# MCU.net
KiCad netlist of a schematic drawn in Altium Designer
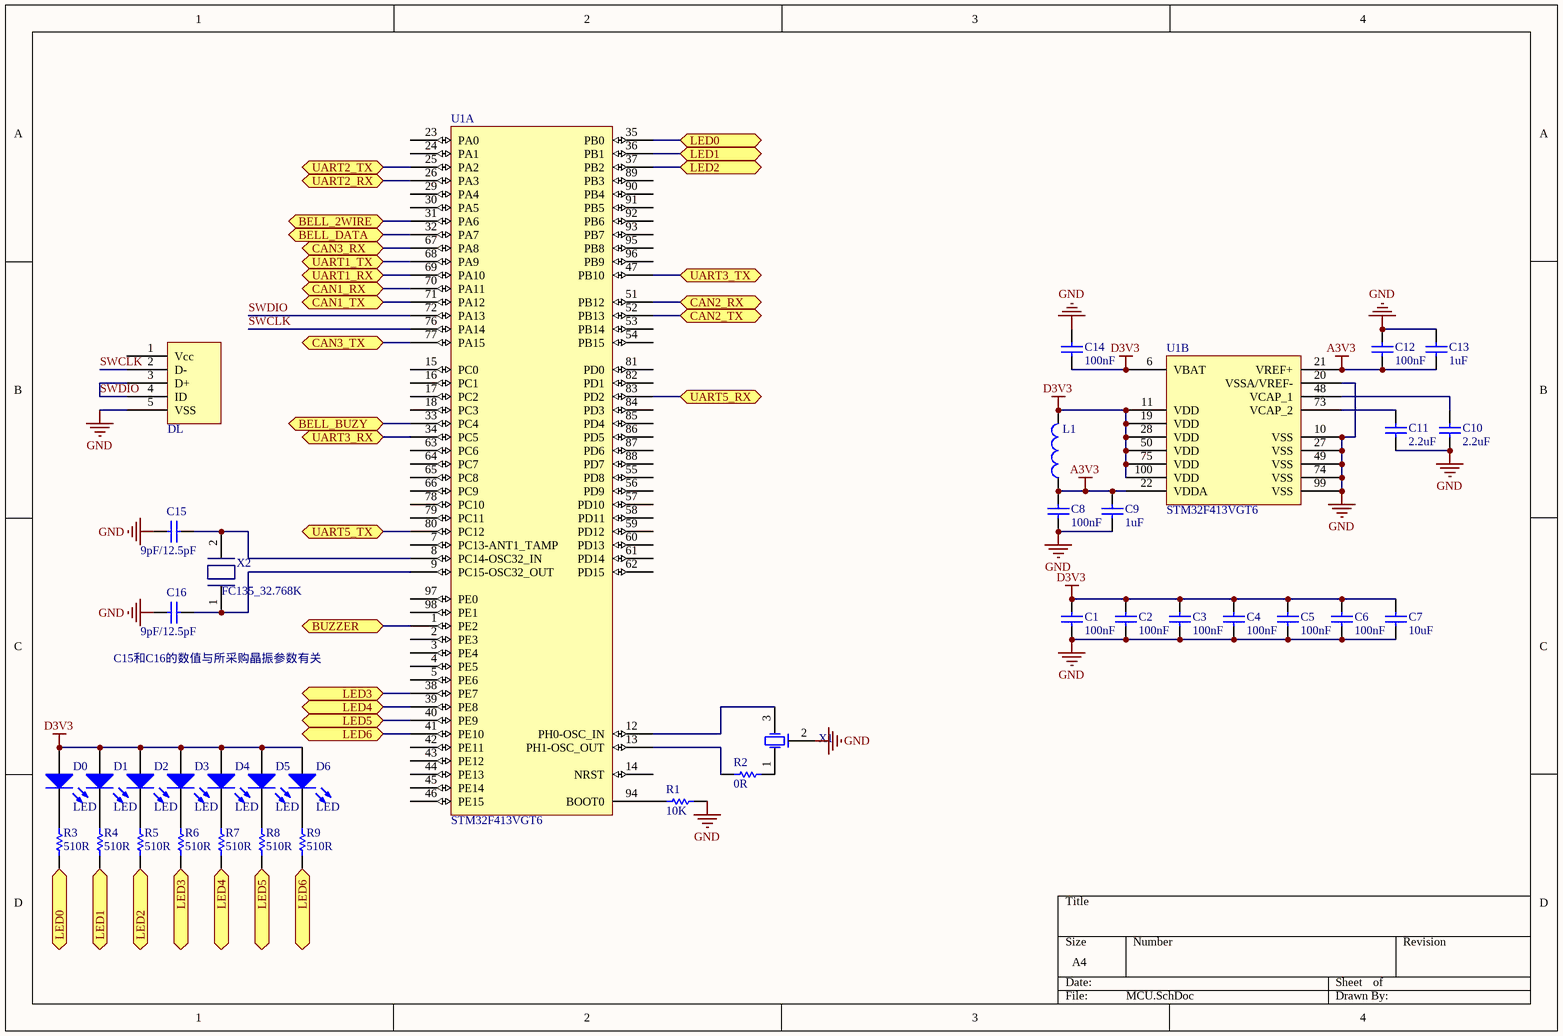
[diagram p0: MCU.SchDoc]

(export (version "E")
  (design (tool "Eeschema 10.0.6"))
  (components
    (comp (ref "C1")
      (value "100nF")
      (footprint "BinFeng:0402")
      (description "Capacitor")
      (fields (field (name "PUBLISHER") "Altium Limited"))
      (libsource (lib "Miscellaneous Devices") (part "Cap"))
    )
    (comp (ref "C2")
      (value "100nF")
      (footprint "BinFeng:0402")
      (description "Capacitor")
      (fields (field (name "PUBLISHER") "Altium Limited"))
      (libsource (lib "Miscellaneous Devices") (part "Cap"))
    )
    (comp (ref "C3")
      (value "100nF")
      (footprint "BinFeng:0402")
      (description "Capacitor")
      (fields (field (name "PUBLISHER") "Altium Limited"))
      (libsource (lib "Miscellaneous Devices") (part "Cap"))
    )
    (comp (ref "C4")
      (value "100nF")
      (footprint "BinFeng:0402")
      (description "Capacitor")
      (fields (field (name "PUBLISHER") "Altium Limited"))
      (libsource (lib "Miscellaneous Devices") (part "Cap"))
    )
    (comp (ref "C5")
      (value "100nF")
      (footprint "BinFeng:0402")
      (description "Capacitor")
      (fields (field (name "PUBLISHER") "Altium Limited"))
      (libsource (lib "Miscellaneous Devices") (part "Cap"))
    )
    (comp (ref "C6")
      (value "100nF")
      (footprint "BinFeng:0402")
      (description "Capacitor")
      (fields (field (name "PUBLISHER") "Altium Limited"))
      (libsource (lib "Miscellaneous Devices") (part "Cap"))
    )
    (comp (ref "C7")
      (value "10uF")
      (footprint "0805")
      (description "Capacitor")
      (fields (field (name "PUBLISHER") "Altium Limited"))
      (libsource (lib "Miscellaneous Devices") (part "Cap"))
    )
    (comp (ref "C8")
      (value "100nF")
      (footprint "BinFeng:0402")
      (description "Capacitor")
      (fields (field (name "PUBLISHER") "Altium Limited"))
      (libsource (lib "Miscellaneous Devices") (part "Cap"))
    )
    (comp (ref "C9")
      (value "1uF")
      (footprint "BinFeng:0402")
      (description "Capacitor")
      (fields (field (name "PUBLISHER") "Altium Limited"))
      (libsource (lib "Miscellaneous Devices") (part "Cap"))
    )
    (comp (ref "C10")
      (value "2.2uF")
      (footprint "BinFeng:0603")
      (description "Capacitor")
      (fields (field (name "PUBLISHER") "Altium Limited"))
      (libsource (lib "Miscellaneous Devices") (part "Cap"))
    )
    (comp (ref "C11")
      (value "2.2uF")
      (footprint "BinFeng:0603")
      (description "Capacitor")
      (fields (field (name "PUBLISHER") "Altium Limited"))
      (libsource (lib "Miscellaneous Devices") (part "Cap"))
    )
    (comp (ref "C12")
      (value "100nF")
      (footprint "BinFeng:0402")
      (description "Capacitor")
      (fields (field (name "PUBLISHER") "Altium Limited"))
      (libsource (lib "Miscellaneous Devices") (part "Cap"))
    )
    (comp (ref "C13")
      (value "1uF")
      (footprint "BinFeng:0402")
      (description "Capacitor")
      (fields (field (name "PUBLISHER") "Altium Limited"))
      (libsource (lib "Miscellaneous Devices") (part "Cap"))
    )
    (comp (ref "C14")
      (value "100nF")
      (footprint "BinFeng:0402")
      (description "Capacitor")
      (fields (field (name "PUBLISHER") "Altium Limited"))
      (libsource (lib "Miscellaneous Devices") (part "Cap"))
    )
    (comp (ref "C15")
      (value "9pF/12.5pF")
      (footprint "BinFeng:0402")
      (description "Capacitor")
      (fields (field (name "PUBLISHER") "Altium Limited"))
      (libsource (lib "Miscellaneous Devices") (part "Cap"))
    )
    (comp (ref "C16")
      (value "9pF/12.5pF")
      (footprint "BinFeng:0402")
      (description "Capacitor")
      (fields (field (name "PUBLISHER") "Altium Limited"))
      (libsource (lib "Miscellaneous Devices") (part "Cap"))
    )
    (comp (ref "D0")
      (value "LED")
      (footprint "1206")
      (description "green LED")
      (fields (field (name "PUBLISHER") "Altium Limited"))
      (libsource (lib "Miscellaneous Devices") (part "LED0"))
    )
    (comp (ref "D1")
      (value "LED")
      (footprint "1206")
      (description "green LED")
      (fields (field (name "PUBLISHER") "Altium Limited"))
      (libsource (lib "Miscellaneous Devices") (part "LED0"))
    )
    (comp (ref "D2")
      (value "LED")
      (footprint "1206")
      (description "green LED")
      (fields (field (name "PUBLISHER") "Altium Limited"))
      (libsource (lib "Miscellaneous Devices") (part "LED0"))
    )
    (comp (ref "D3")
      (value "LED")
      (footprint "1206")
      (description "green LED")
      (fields (field (name "PUBLISHER") "Altium Limited"))
      (libsource (lib "Miscellaneous Devices") (part "LED0"))
    )
    (comp (ref "D4")
      (value "LED")
      (footprint "1206")
      (description "green LED")
      (fields (field (name "PUBLISHER") "Altium Limited"))
      (libsource (lib "Miscellaneous Devices") (part "LED0"))
    )
    (comp (ref "D5")
      (value "LED")
      (footprint "1206")
      (description "green LED")
      (fields (field (name "PUBLISHER") "Altium Limited"))
      (libsource (lib "Miscellaneous Devices") (part "LED0"))
    )
    (comp (ref "D6")
      (value "LED")
      (footprint "1206")
      (description "green LED")
      (fields (field (name "PUBLISHER") "Altium Limited"))
      (libsource (lib "Miscellaneous Devices") (part "LED0"))
    )
    (comp (ref "DL")
      (value "USB_5pin")
      (footprint "USBmicro_B")
      (libsource (lib "BinFeng_Connectors") (part "USB_5pin"))
    )
    (comp (ref "L1")
      (value "BLM15BD221SN1D")
      (footprint "BinFeng:0402")
      (description "muRata ferrite bead")
      (fields (field (name "PUBLISHER") "Altium Limited"))
      (libsource (lib "Miscellaneous Devices") (part "Inductor"))
    )
    (comp (ref "R1")
      (value "10K")
      (footprint "BinFeng:0402")
      (description "Resistor")
      (fields (field (name "PUBLISHER") "Altium Limited"))
      (libsource (lib "Miscellaneous Devices") (part "Res1"))
    )
    (comp (ref "R2")
      (value "0R")
      (footprint "BinFeng:0402")
      (description "Resistor")
      (fields (field (name "PUBLISHER") "Altium Limited"))
      (libsource (lib "Miscellaneous Devices") (part "Res1"))
    )
    (comp (ref "R3")
      (value "510R")
      (footprint "BinFeng:0402")
      (description "Resistor")
      (fields (field (name "PUBLISHER") "Altium Limited"))
      (libsource (lib "Miscellaneous Devices") (part "Res1"))
    )
    (comp (ref "R4")
      (value "510R")
      (footprint "BinFeng:0402")
      (description "Resistor")
      (fields (field (name "PUBLISHER") "Altium Limited"))
      (libsource (lib "Miscellaneous Devices") (part "Res1"))
    )
    (comp (ref "R5")
      (value "510R")
      (footprint "BinFeng:0402")
      (description "Resistor")
      (fields (field (name "PUBLISHER") "Altium Limited"))
      (libsource (lib "Miscellaneous Devices") (part "Res1"))
    )
    (comp (ref "R6")
      (value "510R")
      (footprint "BinFeng:0402")
      (description "Resistor")
      (fields (field (name "PUBLISHER") "Altium Limited"))
      (libsource (lib "Miscellaneous Devices") (part "Res1"))
    )
    (comp (ref "R7")
      (value "510R")
      (footprint "BinFeng:0402")
      (description "Resistor")
      (fields (field (name "PUBLISHER") "Altium Limited"))
      (libsource (lib "Miscellaneous Devices") (part "Res1"))
    )
    (comp (ref "R8")
      (value "510R")
      (footprint "BinFeng:0402")
      (description "Resistor")
      (fields (field (name "PUBLISHER") "Altium Limited"))
      (libsource (lib "Miscellaneous Devices") (part "Res1"))
    )
    (comp (ref "R9")
      (value "510R")
      (footprint "BinFeng:0402")
      (description "Resistor")
      (fields (field (name "PUBLISHER") "Altium Limited"))
      (libsource (lib "Miscellaneous Devices") (part "Res1"))
    )
    (comp (ref "U1")
      (value "STM32F413VGT6")
      (footprint "STM-LQFP100_V")
      (description "ARM Cortex-M4 32-Bit DSP+FPU, 1024 KB Flash, 82 I/Os, 100-Pin LQFP, -40 to 85 degC, Tray")
      (libsource (lib "Altium Content Vault") (part "STM-STM32F413-LQFP-100"))
    )
    (comp (ref "X1")
      (value "8M smd")
      (footprint "8Mhz_XTAL")
      (description "muRata")
      (libsource (lib "Schlib1") (part "8M smd"))
    )
    (comp (ref "X2")
      (value "FC135_32.768K")
      (footprint "FC135")
      (libsource (lib "BinFeng_IC") (part "XTAL_32.768k"))
    )
  )
  (nets
    (net (code "1") (name "/BELL_2WIRE") (class "Default")
      (node (ref "U1") (pin "31") (pinfunction "PA6_31") (pintype "bidirectional"))
    )
    (net (code "2") (name "/BELL_BUZY") (class "Default")
      (node (ref "U1") (pin "33") (pinfunction "PC4_33") (pintype "bidirectional"))
    )
    (net (code "3") (name "/BELL_DATA") (class "Default")
      (node (ref "U1") (pin "32") (pinfunction "PA7_32") (pintype "bidirectional"))
    )
    (net (code "4") (name "/BUZZER") (class "Default")
      (node (ref "U1") (pin "1") (pinfunction "PE2_1") (pintype "bidirectional"))
    )
    (net (code "5") (name "/CAN1_RX") (class "Default")
      (node (ref "U1") (pin "70") (pinfunction "PA11_70") (pintype "bidirectional"))
    )
    (net (code "6") (name "/CAN1_TX") (class "Default")
      (node (ref "U1") (pin "71") (pinfunction "PA12_71") (pintype "bidirectional"))
    )
    (net (code "7") (name "/CAN2_RX") (class "Default")
      (node (ref "U1") (pin "51") (pinfunction "PB12_51") (pintype "bidirectional"))
    )
    (net (code "8") (name "/CAN2_TX") (class "Default")
      (node (ref "U1") (pin "52") (pinfunction "PB13_52") (pintype "bidirectional"))
    )
    (net (code "9") (name "/CAN3_RX") (class "Default")
      (node (ref "U1") (pin "67") (pinfunction "PA8_67") (pintype "bidirectional"))
    )
    (net (code "10") (name "/CAN3_TX") (class "Default")
      (node (ref "U1") (pin "77") (pinfunction "PA15_77") (pintype "bidirectional"))
    )
    (net (code "11") (name "/LED0") (class "Default")
      (node (ref "R3") (pin "1") (pinfunction "1_1") (pintype "passive"))
      (node (ref "U1") (pin "35") (pinfunction "PB0_35") (pintype "bidirectional"))
    )
    (net (code "12") (name "/LED1") (class "Default")
      (node (ref "R4") (pin "1") (pinfunction "1_1") (pintype "passive"))
      (node (ref "U1") (pin "36") (pinfunction "PB1_36") (pintype "bidirectional"))
    )
    (net (code "13") (name "/LED2") (class "Default")
      (node (ref "R5") (pin "1") (pinfunction "1_1") (pintype "passive"))
      (node (ref "U1") (pin "37") (pinfunction "PB2_37") (pintype "bidirectional"))
    )
    (net (code "14") (name "/LED3") (class "Default")
      (node (ref "R6") (pin "1") (pinfunction "1_1") (pintype "passive"))
      (node (ref "U1") (pin "38") (pinfunction "PE7_38") (pintype "bidirectional"))
    )
    (net (code "15") (name "/LED4") (class "Default")
      (node (ref "R7") (pin "1") (pinfunction "1_1") (pintype "passive"))
      (node (ref "U1") (pin "39") (pinfunction "PE8_39") (pintype "bidirectional"))
    )
    (net (code "16") (name "/LED5") (class "Default")
      (node (ref "R8") (pin "1") (pinfunction "1_1") (pintype "passive"))
      (node (ref "U1") (pin "40") (pinfunction "PE9_40") (pintype "bidirectional"))
    )
    (net (code "17") (name "/LED6") (class "Default")
      (node (ref "R9") (pin "1") (pinfunction "1_1") (pintype "passive"))
      (node (ref "U1") (pin "41") (pinfunction "PE10_41") (pintype "bidirectional"))
    )
    (net (code "18") (name "/SWCLK") (class "Default")
      (node (ref "DL") (pin "2") (pinfunction "D-_2") (pintype "passive"))
      (node (ref "U1") (pin "76") (pinfunction "PA14_76") (pintype "bidirectional"))
    )
    (net (code "19") (name "/SWDIO") (class "Default")
      (node (ref "DL") (pin "3") (pinfunction "D+_3") (pintype "passive"))
      (node (ref "DL") (pin "4") (pinfunction "ID_4") (pintype "passive"))
      (node (ref "U1") (pin "72") (pinfunction "PA13_72") (pintype "bidirectional"))
    )
    (net (code "20") (name "/UART1_RX") (class "Default")
      (node (ref "U1") (pin "69") (pinfunction "PA10_69") (pintype "bidirectional"))
    )
    (net (code "21") (name "/UART1_TX") (class "Default")
      (node (ref "U1") (pin "68") (pinfunction "PA9_68") (pintype "bidirectional"))
    )
    (net (code "22") (name "/UART2_RX") (class "Default")
      (node (ref "U1") (pin "26") (pinfunction "PA3_26") (pintype "bidirectional"))
    )
    (net (code "23") (name "/UART2_TX") (class "Default")
      (node (ref "U1") (pin "25") (pinfunction "PA2_25") (pintype "bidirectional"))
    )
    (net (code "24") (name "/UART3_RX") (class "Default")
      (node (ref "U1") (pin "34") (pinfunction "PC5_34") (pintype "bidirectional"))
    )
    (net (code "25") (name "/UART3_TX") (class "Default")
      (node (ref "U1") (pin "47") (pinfunction "PB10_47") (pintype "bidirectional"))
    )
    (net (code "26") (name "/UART5_RX") (class "Default")
      (node (ref "U1") (pin "83") (pinfunction "PD2_83") (pintype "bidirectional"))
    )
    (net (code "27") (name "/UART5_TX") (class "Default")
      (node (ref "U1") (pin "80") (pinfunction "PC12_80") (pintype "bidirectional"))
    )
    (net (code "28") (name "A3V3") (class "Default")
      (node (ref "C12") (pin "1") (pinfunction "1_1") (pintype "passive"))
      (node (ref "C13") (pin "1") (pinfunction "1_1") (pintype "passive"))
      (node (ref "C8") (pin "2") (pinfunction "2_2") (pintype "passive"))
      (node (ref "C9") (pin "2") (pinfunction "2_2") (pintype "passive"))
      (node (ref "L1") (pin "1") (pinfunction "1_1") (pintype "passive"))
      (node (ref "U1") (pin "21") (pinfunction "VREF+_21") (pintype "power_in"))
      (node (ref "U1") (pin "22") (pinfunction "VDDA_22") (pintype "power_in"))
    )
    (net (code "29") (name "D3V3") (class "Default")
      (node (ref "C1") (pin "2") (pinfunction "2_2") (pintype "passive"))
      (node (ref "C14") (pin "1") (pinfunction "1_1") (pintype "passive"))
      (node (ref "C2") (pin "2") (pinfunction "2_2") (pintype "passive"))
      (node (ref "C3") (pin "2") (pinfunction "2_2") (pintype "passive"))
      (node (ref "C4") (pin "2") (pinfunction "2_2") (pintype "passive"))
      (node (ref "C5") (pin "2") (pinfunction "2_2") (pintype "passive"))
      (node (ref "C6") (pin "2") (pinfunction "2_2") (pintype "passive"))
      (node (ref "C7") (pin "2") (pinfunction "2_2") (pintype "passive"))
      (node (ref "D0") (pin "1") (pinfunction "A_1") (pintype "passive"))
      (node (ref "D1") (pin "1") (pinfunction "A_1") (pintype "passive"))
      (node (ref "D2") (pin "1") (pinfunction "A_1") (pintype "passive"))
      (node (ref "D3") (pin "1") (pinfunction "A_1") (pintype "passive"))
      (node (ref "D4") (pin "1") (pinfunction "A_1") (pintype "passive"))
      (node (ref "D5") (pin "1") (pinfunction "A_1") (pintype "passive"))
      (node (ref "D6") (pin "1") (pinfunction "A_1") (pintype "passive"))
      (node (ref "L1") (pin "2") (pinfunction "2_2") (pintype "passive"))
      (node (ref "U1") (pin "100") (pinfunction "VDD_100") (pintype "power_in"))
      (node (ref "U1") (pin "11") (pinfunction "VDD_11") (pintype "power_in"))
      (node (ref "U1") (pin "19") (pinfunction "VDD_19") (pintype "power_in"))
      (node (ref "U1") (pin "28") (pinfunction "VDD_28") (pintype "power_in"))
      (node (ref "U1") (pin "50") (pinfunction "VDD_50") (pintype "power_in"))
      (node (ref "U1") (pin "6") (pinfunction "VBAT_6") (pintype "power_in"))
      (node (ref "U1") (pin "75") (pinfunction "VDD_75") (pintype "power_in"))
    )
    (net (code "30") (name "GND") (class "Default")
      (node (ref "C1") (pin "1") (pinfunction "1_1") (pintype "passive"))
      (node (ref "C10") (pin "1") (pinfunction "1_1") (pintype "passive"))
      (node (ref "C11") (pin "1") (pinfunction "1_1") (pintype "passive"))
      (node (ref "C12") (pin "2") (pinfunction "2_2") (pintype "passive"))
      (node (ref "C13") (pin "2") (pinfunction "2_2") (pintype "passive"))
      (node (ref "C14") (pin "2") (pinfunction "2_2") (pintype "passive"))
      (node (ref "C15") (pin "2") (pinfunction "2_2") (pintype "passive"))
      (node (ref "C16") (pin "2") (pinfunction "2_2") (pintype "passive"))
      (node (ref "C2") (pin "1") (pinfunction "1_1") (pintype "passive"))
      (node (ref "C3") (pin "1") (pinfunction "1_1") (pintype "passive"))
      (node (ref "C4") (pin "1") (pinfunction "1_1") (pintype "passive"))
      (node (ref "C5") (pin "1") (pinfunction "1_1") (pintype "passive"))
      (node (ref "C6") (pin "1") (pinfunction "1_1") (pintype "passive"))
      (node (ref "C7") (pin "1") (pinfunction "1_1") (pintype "passive"))
      (node (ref "C8") (pin "1") (pinfunction "1_1") (pintype "passive"))
      (node (ref "C9") (pin "1") (pinfunction "1_1") (pintype "passive"))
      (node (ref "DL") (pin "5") (pinfunction "VSS_5") (pintype "passive"))
      (node (ref "R1") (pin "2") (pinfunction "2_2") (pintype "passive"))
      (node (ref "U1") (pin "10") (pinfunction "VSS_10") (pintype "power_in"))
      (node (ref "U1") (pin "20") (pinfunction "VSSA/VREF-_20") (pintype "power_in"))
      (node (ref "U1") (pin "27") (pinfunction "VSS_27") (pintype "power_in"))
      (node (ref "U1") (pin "49") (pinfunction "VSS_49") (pintype "power_in"))
      (node (ref "U1") (pin "74") (pinfunction "VSS_74") (pintype "power_in"))
      (node (ref "U1") (pin "99") (pinfunction "VSS_99") (pintype "power_in"))
      (node (ref "X1") (pin "2") (pinfunction "GND_2") (pintype "passive"))
    )
    (net (code "31") (name "Net-(D0-K)") (class "Default")
      (node (ref "D0") (pin "2") (pinfunction "K_2") (pintype "passive"))
      (node (ref "R3") (pin "2") (pinfunction "2_2") (pintype "passive"))
    )
    (net (code "32") (name "Net-(D1-K)") (class "Default")
      (node (ref "D1") (pin "2") (pinfunction "K_2") (pintype "passive"))
      (node (ref "R4") (pin "2") (pinfunction "2_2") (pintype "passive"))
    )
    (net (code "33") (name "Net-(D2-K)") (class "Default")
      (node (ref "D2") (pin "2") (pinfunction "K_2") (pintype "passive"))
      (node (ref "R5") (pin "2") (pinfunction "2_2") (pintype "passive"))
    )
    (net (code "34") (name "Net-(D3-K)") (class "Default")
      (node (ref "D3") (pin "2") (pinfunction "K_2") (pintype "passive"))
      (node (ref "R6") (pin "2") (pinfunction "2_2") (pintype "passive"))
    )
    (net (code "35") (name "Net-(D4-K)") (class "Default")
      (node (ref "D4") (pin "2") (pinfunction "K_2") (pintype "passive"))
      (node (ref "R7") (pin "2") (pinfunction "2_2") (pintype "passive"))
    )
    (net (code "36") (name "Net-(D5-K)") (class "Default")
      (node (ref "D5") (pin "2") (pinfunction "K_2") (pintype "passive"))
      (node (ref "R8") (pin "2") (pinfunction "2_2") (pintype "passive"))
    )
    (net (code "37") (name "Net-(D6-K)") (class "Default")
      (node (ref "D6") (pin "2") (pinfunction "K_2") (pintype "passive"))
      (node (ref "R9") (pin "2") (pinfunction "2_2") (pintype "passive"))
    )
    (net (code "38") (name "Net-(U1A-BOOT0)") (class "Default")
      (node (ref "R1") (pin "1") (pinfunction "1_1") (pintype "passive"))
      (node (ref "U1") (pin "94") (pinfunction "BOOT0_94") (pintype "passive"))
    )
    (net (code "39") (name "Net-(U1A-PC14-OSC32_IN)") (class "Default")
      (node (ref "C15") (pin "1") (pinfunction "1_1") (pintype "passive"))
      (node (ref "U1") (pin "8") (pinfunction "PC14-OSC32_IN_8") (pintype "bidirectional"))
      (node (ref "X2") (pin "2") (pinfunction "2_2") (pintype "passive"))
    )
    (net (code "40") (name "Net-(U1A-PC15-OSC32_OUT)") (class "Default")
      (node (ref "C16") (pin "1") (pinfunction "1_1") (pintype "passive"))
      (node (ref "U1") (pin "9") (pinfunction "PC15-OSC32_OUT_9") (pintype "bidirectional"))
      (node (ref "X2") (pin "1") (pinfunction "1_1") (pintype "passive"))
    )
    (net (code "41") (name "Net-(U1A-PH0-OSC_IN)") (class "Default")
      (node (ref "U1") (pin "12") (pinfunction "PH0-OSC_IN_12") (pintype "bidirectional"))
      (node (ref "X1") (pin "3") (pinfunction "OSC2_3") (pintype "passive"))
    )
    (net (code "42") (name "Net-(U1A-PH1-OSC_OUT)") (class "Default")
      (node (ref "R2") (pin "2") (pinfunction "2_2") (pintype "passive"))
      (node (ref "U1") (pin "13") (pinfunction "PH1-OSC_OUT_13") (pintype "bidirectional"))
    )
    (net (code "43") (name "Net-(U1B-VCAP_1)") (class "Default")
      (node (ref "C10") (pin "2") (pinfunction "2_2") (pintype "passive"))
      (node (ref "U1") (pin "48") (pinfunction "VCAP_1_48") (pintype "passive"))
    )
    (net (code "44") (name "Net-(U1B-VCAP_2)") (class "Default")
      (node (ref "C11") (pin "2") (pinfunction "2_2") (pintype "passive"))
      (node (ref "U1") (pin "73") (pinfunction "VCAP_2_73") (pintype "passive"))
    )
    (net (code "45") (name "Net-(X1-OSC1)") (class "Default")
      (node (ref "R2") (pin "1") (pinfunction "1_1") (pintype "passive"))
      (node (ref "X1") (pin "1") (pinfunction "OSC1_1") (pintype "passive"))
    )
    (net (code "46") (name "unconnected-(DL-Vcc-Pad1)") (class "Default")
      (node (ref "DL") (pin "1") (pinfunction "Vcc_1") (pintype "passive"))
    )
    (net (code "47") (name "unconnected-(U1A-NRST-Pad14)") (class "Default")
      (node (ref "U1") (pin "14") (pinfunction "NRST_14") (pintype "bidirectional"))
    )
    (net (code "48") (name "unconnected-(U1A-PA0-Pad23)") (class "Default")
      (node (ref "U1") (pin "23") (pinfunction "PA0_23") (pintype "bidirectional"))
    )
    (net (code "49") (name "unconnected-(U1A-PA1-Pad24)") (class "Default")
      (node (ref "U1") (pin "24") (pinfunction "PA1_24") (pintype "bidirectional"))
    )
    (net (code "50") (name "unconnected-(U1A-PA4-Pad29)") (class "Default")
      (node (ref "U1") (pin "29") (pinfunction "PA4_29") (pintype "bidirectional"))
    )
    (net (code "51") (name "unconnected-(U1A-PA5-Pad30)") (class "Default")
      (node (ref "U1") (pin "30") (pinfunction "PA5_30") (pintype "bidirectional"))
    )
    (net (code "52") (name "unconnected-(U1A-PB3-Pad89)") (class "Default")
      (node (ref "U1") (pin "89") (pinfunction "PB3_89") (pintype "bidirectional"))
    )
    (net (code "53") (name "unconnected-(U1A-PB4-Pad90)") (class "Default")
      (node (ref "U1") (pin "90") (pinfunction "PB4_90") (pintype "bidirectional"))
    )
    (net (code "54") (name "unconnected-(U1A-PB5-Pad91)") (class "Default")
      (node (ref "U1") (pin "91") (pinfunction "PB5_91") (pintype "bidirectional"))
    )
    (net (code "55") (name "unconnected-(U1A-PB6-Pad92)") (class "Default")
      (node (ref "U1") (pin "92") (pinfunction "PB6_92") (pintype "bidirectional"))
    )
    (net (code "56") (name "unconnected-(U1A-PB7-Pad93)") (class "Default")
      (node (ref "U1") (pin "93") (pinfunction "PB7_93") (pintype "bidirectional"))
    )
    (net (code "57") (name "unconnected-(U1A-PB8-Pad95)") (class "Default")
      (node (ref "U1") (pin "95") (pinfunction "PB8_95") (pintype "bidirectional"))
    )
    (net (code "58") (name "unconnected-(U1A-PB9-Pad96)") (class "Default")
      (node (ref "U1") (pin "96") (pinfunction "PB9_96") (pintype "bidirectional"))
    )
    (net (code "59") (name "unconnected-(U1A-PB14-Pad53)") (class "Default")
      (node (ref "U1") (pin "53") (pinfunction "PB14_53") (pintype "bidirectional"))
    )
    (net (code "60") (name "unconnected-(U1A-PB15-Pad54)") (class "Default")
      (node (ref "U1") (pin "54") (pinfunction "PB15_54") (pintype "bidirectional"))
    )
    (net (code "61") (name "unconnected-(U1A-PC0-Pad15)") (class "Default")
      (node (ref "U1") (pin "15") (pinfunction "PC0_15") (pintype "bidirectional"))
    )
    (net (code "62") (name "unconnected-(U1A-PC1-Pad16)") (class "Default")
      (node (ref "U1") (pin "16") (pinfunction "PC1_16") (pintype "bidirectional"))
    )
    (net (code "63") (name "unconnected-(U1A-PC2-Pad17)") (class "Default")
      (node (ref "U1") (pin "17") (pinfunction "PC2_17") (pintype "bidirectional"))
    )
    (net (code "64") (name "unconnected-(U1A-PC3-Pad18)") (class "Default")
      (node (ref "U1") (pin "18") (pinfunction "PC3_18") (pintype "bidirectional"))
    )
    (net (code "65") (name "unconnected-(U1A-PC6-Pad63)") (class "Default")
      (node (ref "U1") (pin "63") (pinfunction "PC6_63") (pintype "bidirectional"))
    )
    (net (code "66") (name "unconnected-(U1A-PC7-Pad64)") (class "Default")
      (node (ref "U1") (pin "64") (pinfunction "PC7_64") (pintype "bidirectional"))
    )
    (net (code "67") (name "unconnected-(U1A-PC8-Pad65)") (class "Default")
      (node (ref "U1") (pin "65") (pinfunction "PC8_65") (pintype "bidirectional"))
    )
    (net (code "68") (name "unconnected-(U1A-PC9-Pad66)") (class "Default")
      (node (ref "U1") (pin "66") (pinfunction "PC9_66") (pintype "bidirectional"))
    )
    (net (code "69") (name "unconnected-(U1A-PC10-Pad78)") (class "Default")
      (node (ref "U1") (pin "78") (pinfunction "PC10_78") (pintype "bidirectional"))
    )
    (net (code "70") (name "unconnected-(U1A-PC11-Pad79)") (class "Default")
      (node (ref "U1") (pin "79") (pinfunction "PC11_79") (pintype "bidirectional"))
    )
    (net (code "71") (name "unconnected-(U1A-PC13-ANT1_TAMP-Pad7)") (class "Default")
      (node (ref "U1") (pin "7") (pinfunction "PC13-ANT1_TAMP_7") (pintype "bidirectional"))
    )
    (net (code "72") (name "unconnected-(U1A-PD0-Pad81)") (class "Default")
      (node (ref "U1") (pin "81") (pinfunction "PD0_81") (pintype "bidirectional"))
    )
    (net (code "73") (name "unconnected-(U1A-PD1-Pad82)") (class "Default")
      (node (ref "U1") (pin "82") (pinfunction "PD1_82") (pintype "bidirectional"))
    )
    (net (code "74") (name "unconnected-(U1A-PD3-Pad84)") (class "Default")
      (node (ref "U1") (pin "84") (pinfunction "PD3_84") (pintype "bidirectional"))
    )
    (net (code "75") (name "unconnected-(U1A-PD4-Pad85)") (class "Default")
      (node (ref "U1") (pin "85") (pinfunction "PD4_85") (pintype "bidirectional"))
    )
    (net (code "76") (name "unconnected-(U1A-PD5-Pad86)") (class "Default")
      (node (ref "U1") (pin "86") (pinfunction "PD5_86") (pintype "bidirectional"))
    )
    (net (code "77") (name "unconnected-(U1A-PD6-Pad87)") (class "Default")
      (node (ref "U1") (pin "87") (pinfunction "PD6_87") (pintype "bidirectional"))
    )
    (net (code "78") (name "unconnected-(U1A-PD7-Pad88)") (class "Default")
      (node (ref "U1") (pin "88") (pinfunction "PD7_88") (pintype "bidirectional"))
    )
    (net (code "79") (name "unconnected-(U1A-PD8-Pad55)") (class "Default")
      (node (ref "U1") (pin "55") (pinfunction "PD8_55") (pintype "bidirectional"))
    )
    (net (code "80") (name "unconnected-(U1A-PD9-Pad56)") (class "Default")
      (node (ref "U1") (pin "56") (pinfunction "PD9_56") (pintype "bidirectional"))
    )
    (net (code "81") (name "unconnected-(U1A-PD10-Pad57)") (class "Default")
      (node (ref "U1") (pin "57") (pinfunction "PD10_57") (pintype "bidirectional"))
    )
    (net (code "82") (name "unconnected-(U1A-PD11-Pad58)") (class "Default")
      (node (ref "U1") (pin "58") (pinfunction "PD11_58") (pintype "bidirectional"))
    )
    (net (code "83") (name "unconnected-(U1A-PD12-Pad59)") (class "Default")
      (node (ref "U1") (pin "59") (pinfunction "PD12_59") (pintype "bidirectional"))
    )
    (net (code "84") (name "unconnected-(U1A-PD13-Pad60)") (class "Default")
      (node (ref "U1") (pin "60") (pinfunction "PD13_60") (pintype "bidirectional"))
    )
    (net (code "85") (name "unconnected-(U1A-PD14-Pad61)") (class "Default")
      (node (ref "U1") (pin "61") (pinfunction "PD14_61") (pintype "bidirectional"))
    )
    (net (code "86") (name "unconnected-(U1A-PD15-Pad62)") (class "Default")
      (node (ref "U1") (pin "62") (pinfunction "PD15_62") (pintype "bidirectional"))
    )
    (net (code "87") (name "unconnected-(U1A-PE0-Pad97)") (class "Default")
      (node (ref "U1") (pin "97") (pinfunction "PE0_97") (pintype "bidirectional"))
    )
    (net (code "88") (name "unconnected-(U1A-PE1-Pad98)") (class "Default")
      (node (ref "U1") (pin "98") (pinfunction "PE1_98") (pintype "bidirectional"))
    )
    (net (code "89") (name "unconnected-(U1A-PE3-Pad2)") (class "Default")
      (node (ref "U1") (pin "2") (pinfunction "PE3_2") (pintype "bidirectional"))
    )
    (net (code "90") (name "unconnected-(U1A-PE4-Pad3)") (class "Default")
      (node (ref "U1") (pin "3") (pinfunction "PE4_3") (pintype "bidirectional"))
    )
    (net (code "91") (name "unconnected-(U1A-PE5-Pad4)") (class "Default")
      (node (ref "U1") (pin "4") (pinfunction "PE5_4") (pintype "bidirectional"))
    )
    (net (code "92") (name "unconnected-(U1A-PE6-Pad5)") (class "Default")
      (node (ref "U1") (pin "5") (pinfunction "PE6_5") (pintype "bidirectional"))
    )
    (net (code "93") (name "unconnected-(U1A-PE11-Pad42)") (class "Default")
      (node (ref "U1") (pin "42") (pinfunction "PE11_42") (pintype "bidirectional"))
    )
    (net (code "94") (name "unconnected-(U1A-PE12-Pad43)") (class "Default")
      (node (ref "U1") (pin "43") (pinfunction "PE12_43") (pintype "bidirectional"))
    )
    (net (code "95") (name "unconnected-(U1A-PE13-Pad44)") (class "Default")
      (node (ref "U1") (pin "44") (pinfunction "PE13_44") (pintype "bidirectional"))
    )
    (net (code "96") (name "unconnected-(U1A-PE14-Pad45)") (class "Default")
      (node (ref "U1") (pin "45") (pinfunction "PE14_45") (pintype "bidirectional"))
    )
    (net (code "97") (name "unconnected-(U1A-PE15-Pad46)") (class "Default")
      (node (ref "U1") (pin "46") (pinfunction "PE15_46") (pintype "bidirectional"))
    )
  )
)
